# PCB_4L_-_Revision_History.net
KiCad netlist of a schematic drawn in Altium Designer
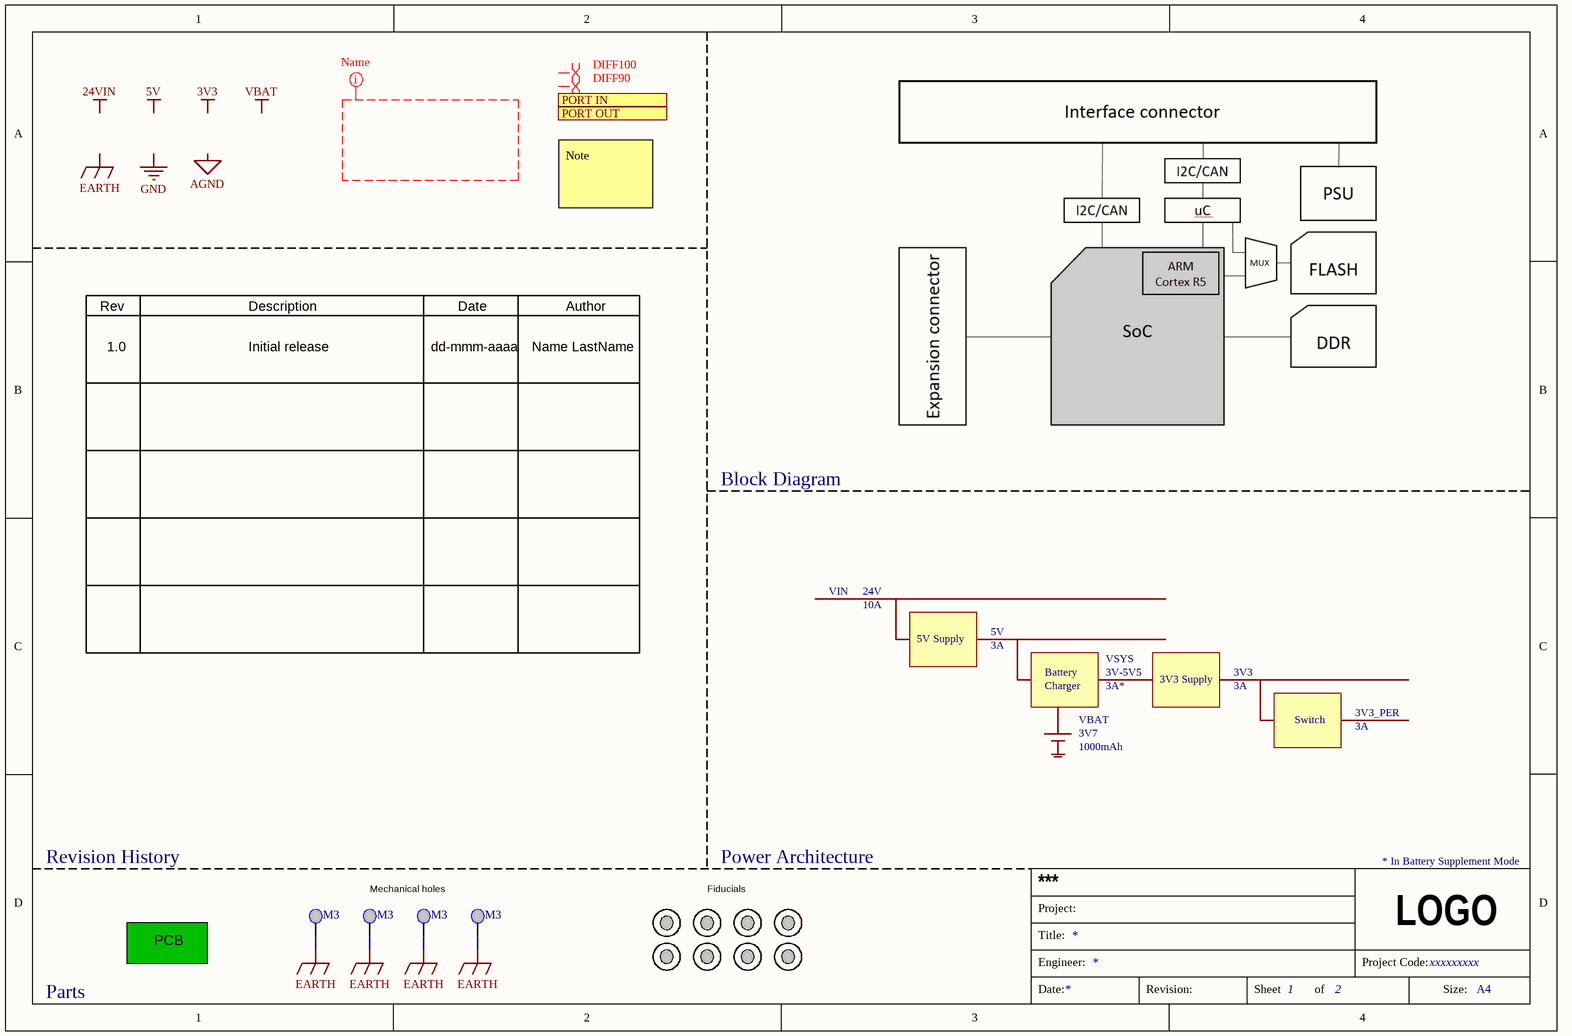
[diagram p0: _PCB_4L - Revision History.SchDoc]

(export (version "E")
  (design (tool "Eeschema 10.0.6"))
  (components
    (comp (ref "FD1")
      (value "Fiducial 1.3")
      (footprint "Fiducial 1.3mm")
      (description "Fiducial 1.3mm")
      (libsource (lib "Miscelaneos") (part "Fiducial 1.3"))
    )
    (comp (ref "FD2")
      (value "Fiducial 1.3")
      (footprint "Fiducial 1.3mm")
      (description "Fiducial 1.3mm")
      (libsource (lib "Miscelaneos") (part "Fiducial 1.3"))
    )
    (comp (ref "FD3")
      (value "Fiducial 1.3")
      (footprint "Fiducial 1.3mm")
      (description "Fiducial 1.3mm")
      (libsource (lib "Miscelaneos") (part "Fiducial 1.3"))
    )
    (comp (ref "FD4")
      (value "Fiducial 1.3")
      (footprint "Fiducial 1.3mm")
      (description "Fiducial 1.3mm")
      (libsource (lib "Miscelaneos") (part "Fiducial 1.3"))
    )
    (comp (ref "FD5")
      (value "Fiducial 1.3")
      (footprint "Fiducial 1.3mm")
      (description "Fiducial 1.3mm")
      (libsource (lib "Miscelaneos") (part "Fiducial 1.3"))
    )
    (comp (ref "FD6")
      (value "Fiducial 1.3")
      (footprint "Fiducial 1.3mm")
      (description "Fiducial 1.3mm")
      (libsource (lib "Miscelaneos") (part "Fiducial 1.3"))
    )
    (comp (ref "FD7")
      (value "Fiducial 1.3")
      (footprint "Fiducial 1.3mm")
      (description "Fiducial 1.3mm")
      (libsource (lib "Miscelaneos") (part "Fiducial 1.3"))
    )
    (comp (ref "FD8")
      (value "Fiducial 1.3")
      (footprint "Fiducial 1.3mm")
      (description "Fiducial 1.3mm")
      (libsource (lib "Miscelaneos") (part "Fiducial 1.3"))
    )
    (comp (ref "MEC1")
      (value "M3")
      (footprint "M3 hole")
      (description "M3 hole")
      (libsource (lib "Miscelaneos") (part "M3 hole"))
    )
    (comp (ref "MEC2")
      (value "M3")
      (footprint "M3 hole")
      (description "M3 hole")
      (libsource (lib "Miscelaneos") (part "M3 hole"))
    )
    (comp (ref "MEC3")
      (value "M3")
      (footprint "M3 hole")
      (description "M3 hole")
      (libsource (lib "Miscelaneos") (part "M3 hole"))
    )
    (comp (ref "MEC4")
      (value "M3")
      (footprint "M3 hole")
      (description "M3 hole")
      (libsource (lib "Miscelaneos") (part "M3 hole"))
    )
    (comp (ref "_PCB1") (value "PCB spec") (description "PCB") (libsource (lib "Miscellaneous") (part "PCB")))
  )
  (nets
    (net (code "7") (name "EARTH") (class "Default")
      (node (ref "MEC1") (pin "0") (pinfunction "0_0") (pintype "passive"))
      (node (ref "MEC2") (pin "0") (pinfunction "0_0") (pintype "passive"))
      (node (ref "MEC3") (pin "0") (pinfunction "0_0") (pintype "passive"))
      (node (ref "MEC4") (pin "0") (pinfunction "0_0") (pintype "passive"))
    )
  )
)
